# MCU.net
KiCad netlist of a schematic drawn in Altium Designer
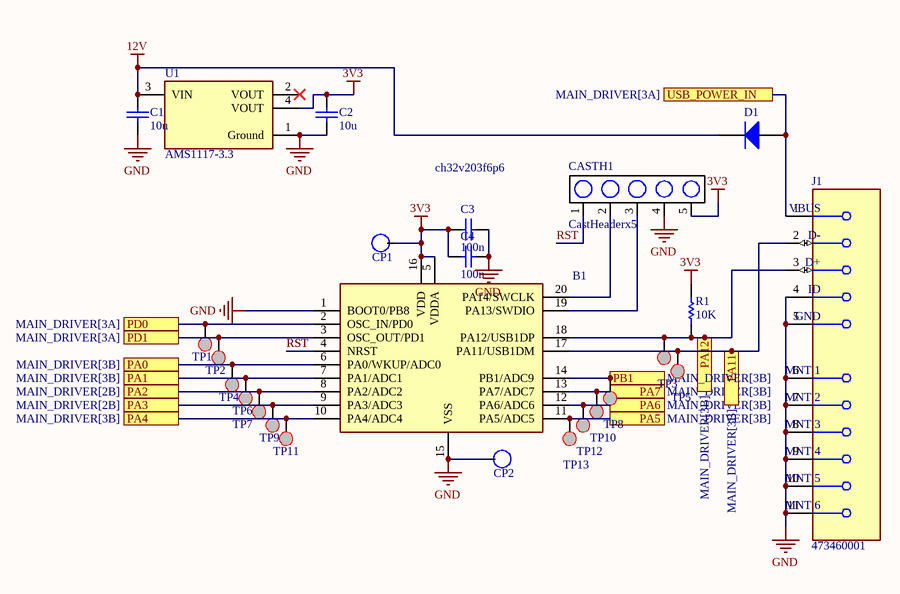
[diagram p0: MCU.SchDoc]

(export (version "E")
  (design (tool "Eeschema 10.0.6"))
  (components
    (comp (ref "B1")
      (value "ch32v203f6p6")
      (footprint "SOP65P640X110-20N")
      (description "144MHz, Industrial-grade general-purpose microcontrollers TSSOP20 Package")
      (libsource (lib "ch32v203f6p6") (part "ch32v203f6p6"))
    )
    (comp (ref "C1")
      (value "10u")
      (footprint "CAP FILM 0603_1608")
      (description "Capacitor")
      (libsource (lib "Simulation Generic Components") (part "Capacitor"))
    )
    (comp (ref "C2")
      (value "10u")
      (footprint "CAP FILM 0603_1608")
      (description "Capacitor")
      (libsource (lib "Simulation Generic Components") (part "Capacitor"))
    )
    (comp (ref "C3")
      (value "100n")
      (footprint "SMD-0603-RES")
      (description "Capacitor")
      (libsource (lib "Simulation Generic Components") (part "Capacitor"))
    )
    (comp (ref "C4")
      (value "100n")
      (footprint "SMD-0603-RES")
      (description "Capacitor")
      (libsource (lib "Simulation Generic Components") (part "Capacitor"))
    )
    (comp (ref "CASTH1")
      (value "CastHeaderx5")
      (footprint "CASTHEADERX5")
      (libsource (lib "castellated_headers") (part "CastHeaderx5"))
    )
    (comp (ref "CP1")
      (value "CONNECT_PAD")
      (footprint "PAD_SQUARE")
      (libsource (lib "solderpad") (part "CONNECT_PAD"))
    )
    (comp (ref "CP2")
      (value "CONNECT_PAD")
      (footprint "PAD_SQUARE")
      (libsource (lib "solderpad") (part "CONNECT_PAD"))
    )
    (comp (ref "D1")
      (value "FR107")
      (footprint "SODFL365X110-2N")
      (description "Diode")
      (libsource (lib "Simulation Generic Components") (part "Diode"))
    )
    (comp (ref "J1")
      (value "473460001")
      (footprint "FP-473460001-MFG")
      (description "CONN RCPT USB2.0 MICRO B SMD R/A")
      (fields
        (field (name "OCTOPART") "https://octopart.com/47346-0001-molex-7164928")
        (field (name "MANUFACTURER") "Molex")
      )
      (libsource (lib "Altium Content Vault") (part "53ae1f1d9b557310b43ca686e5bb76a"))
    )
    (comp (ref "R1")
      (value "10K")
      (footprint "SMD-0603-RES")
      (description "Resistor")
      (libsource (lib "Simulation Generic Components") (part "Resistor"))
    )
    (comp (ref "TP1") (value "~") (footprint "ROUND_SMALL") (libsource (lib "solderpad") (part "TEST_PAD")))
    (comp (ref "TP2") (value "~") (footprint "ROUND_SMALL") (libsource (lib "solderpad") (part "TEST_PAD")))
    (comp (ref "TP3") (value "~") (footprint "ROUND_SMALL") (libsource (lib "solderpad") (part "TEST_PAD")))
    (comp (ref "TP4") (value "~") (footprint "ROUND_SMALL") (libsource (lib "solderpad") (part "TEST_PAD")))
    (comp (ref "TP5") (value "~") (footprint "ROUND_SMALL") (libsource (lib "solderpad") (part "TEST_PAD")))
    (comp (ref "TP6") (value "~") (footprint "ROUND_SMALL") (libsource (lib "solderpad") (part "TEST_PAD")))
    (comp (ref "TP7") (value "~") (footprint "ROUND_SMALL") (libsource (lib "solderpad") (part "TEST_PAD")))
    (comp (ref "TP8") (value "~") (footprint "ROUND_SMALL") (libsource (lib "solderpad") (part "TEST_PAD")))
    (comp (ref "TP9") (value "~") (footprint "ROUND_SMALL") (libsource (lib "solderpad") (part "TEST_PAD")))
    (comp (ref "TP10") (value "~") (footprint "ROUND_SMALL") (libsource (lib "solderpad") (part "TEST_PAD")))
    (comp (ref "TP11") (value "~") (footprint "ROUND_SMALL") (libsource (lib "solderpad") (part "TEST_PAD")))
    (comp (ref "TP12") (value "~") (footprint "ROUND_SMALL") (libsource (lib "solderpad") (part "TEST_PAD")))
    (comp (ref "TP13") (value "~") (footprint "ROUND_SMALL") (libsource (lib "solderpad") (part "TEST_PAD")))
    (comp (ref "U1")
      (value "AMS1117-3.3")
      (footprint "FP-AMS1117-IPC_C")
      (description "LDO Voltage Regulators 1A, 3.3V")
      (fields
        (field (name "OCTOPART") "https://octopart.com/ams1117-3.3-advanced+monolithic+systems-25899300")
        (field (name "MANUFACTURER") "Advanced Monolithic Systems")
      )
      (libsource (lib "Altium Content Vault") (part "8bdbb5f8e77002000e30dd2845d0354"))
    )
  )
  (nets
    (net (code "1") (name "/PA0") (class "Default")
      (node (ref "B1") (pin "6") (pinfunction "PA0/WKUP/ADC0_6") (pintype "passive"))
      (node (ref "TP4") (pin "1") (pinfunction "Test_Point_1") (pintype "passive"))
    )
    (net (code "2") (name "/PA1") (class "Default")
      (node (ref "B1") (pin "7") (pinfunction "PA1/ADC1_7") (pintype "passive"))
      (node (ref "TP6") (pin "1") (pinfunction "Test_Point_1") (pintype "passive"))
    )
    (net (code "3") (name "/PA2") (class "Default")
      (node (ref "B1") (pin "8") (pinfunction "PA2/ADC2_8") (pintype "passive"))
      (node (ref "TP7") (pin "1") (pinfunction "Test_Point_1") (pintype "passive"))
    )
    (net (code "4") (name "/PA3") (class "Default")
      (node (ref "B1") (pin "9") (pinfunction "PA3/ADC3_9") (pintype "passive"))
      (node (ref "TP9") (pin "1") (pinfunction "Test_Point_1") (pintype "passive"))
    )
    (net (code "5") (name "/PA4") (class "Default")
      (node (ref "B1") (pin "10") (pinfunction "PA4/ADC4_10") (pintype "passive"))
      (node (ref "TP11") (pin "1") (pinfunction "Test_Point_1") (pintype "passive"))
    )
    (net (code "6") (name "/PA5") (class "Default")
      (node (ref "B1") (pin "11") (pinfunction "PA5/ADC5_11") (pintype "passive"))
      (node (ref "TP13") (pin "1") (pinfunction "Test_Point_1") (pintype "passive"))
    )
    (net (code "7") (name "/PA6") (class "Default")
      (node (ref "B1") (pin "12") (pinfunction "PA6/ADC6_12") (pintype "passive"))
      (node (ref "TP12") (pin "1") (pinfunction "Test_Point_1") (pintype "passive"))
    )
    (net (code "8") (name "/PA7") (class "Default")
      (node (ref "B1") (pin "13") (pinfunction "PA7/ADC7_13") (pintype "passive"))
      (node (ref "TP10") (pin "1") (pinfunction "Test_Point_1") (pintype "passive"))
    )
    (net (code "9") (name "/PA11") (class "Default")
      (node (ref "B1") (pin "17") (pinfunction "PA11/USB1DM_17") (pintype "passive"))
      (node (ref "J1") (pin "2") (pinfunction "D+_2") (pintype "bidirectional"))
      (node (ref "TP5") (pin "1") (pinfunction "Test_Point_1") (pintype "passive"))
    )
    (net (code "10") (name "/PA12") (class "Default")
      (node (ref "B1") (pin "18") (pinfunction "PA12/USB1DP_18") (pintype "passive"))
      (node (ref "J1") (pin "3") (pinfunction "D-_3") (pintype "bidirectional"))
      (node (ref "R1") (pin "1") (pinfunction "1_1") (pintype "passive"))
      (node (ref "TP3") (pin "1") (pinfunction "Test_Point_1") (pintype "passive"))
    )
    (net (code "11") (name "/PB1") (class "Default")
      (node (ref "B1") (pin "14") (pinfunction "PB1/ADC9_14") (pintype "passive"))
      (node (ref "TP8") (pin "1") (pinfunction "Test_Point_1") (pintype "passive"))
    )
    (net (code "12") (name "/PD0") (class "Default")
      (node (ref "B1") (pin "2") (pinfunction "OSC_IN/PD0_2") (pintype "passive"))
      (node (ref "TP1") (pin "1") (pinfunction "Test_Point_1") (pintype "passive"))
    )
    (net (code "13") (name "/PD1") (class "Default")
      (node (ref "B1") (pin "3") (pinfunction "OSC_OUT/PD1_3") (pintype "passive"))
      (node (ref "TP2") (pin "1") (pinfunction "Test_Point_1") (pintype "passive"))
    )
    (net (code "14") (name "/RST") (class "Default")
      (node (ref "B1") (pin "4") (pinfunction "NRST_4") (pintype "passive"))
      (node (ref "CASTH1") (pin "1") (pinfunction "1_1") (pintype "passive"))
    )
    (net (code "15") (name "/USB_POWER_IN") (class "Default")
      (node (ref "D1") (pin "1") (pinfunction "A_1") (pintype "passive"))
      (node (ref "J1") (pin "1") (pinfunction "VBUS_1") (pintype "power_in"))
    )
    (net (code "16") (name "3V3") (class "Default")
      (node (ref "B1") (pin "16") (pinfunction "VDD_16") (pintype "passive"))
      (node (ref "B1") (pin "5") (pinfunction "VDDA_5") (pintype "passive"))
      (node (ref "C2") (pin "2") (pinfunction "2_2") (pintype "passive"))
      (node (ref "C3") (pin "1") (pinfunction "1_1") (pintype "passive"))
      (node (ref "C4") (pin "1") (pinfunction "1_1") (pintype "passive"))
      (node (ref "CASTH1") (pin "5") (pinfunction "5_5") (pintype "passive"))
      (node (ref "CP1") (pin "1") (pinfunction "1_1") (pintype "passive"))
      (node (ref "R1") (pin "2") (pinfunction "2_2") (pintype "passive"))
      (node (ref "U1") (pin "4") (pinfunction "VOUT_4") (pintype "passive"))
    )
    (net (code "17") (name "12V") (class "Default")
      (node (ref "C1") (pin "2") (pinfunction "2_2") (pintype "passive"))
      (node (ref "D1") (pin "2") (pinfunction "K_2") (pintype "passive"))
      (node (ref "U1") (pin "3") (pinfunction "VIN_3") (pintype "power_in"))
    )
    (net (code "18") (name "GND") (class "Default")
      (node (ref "B1") (pin "1") (pinfunction "BOOT0/PB8_1") (pintype "passive"))
      (node (ref "B1") (pin "15") (pinfunction "VSS_15") (pintype "passive"))
      (node (ref "C1") (pin "1") (pinfunction "1_1") (pintype "passive"))
      (node (ref "C2") (pin "1") (pinfunction "1_1") (pintype "passive"))
      (node (ref "C3") (pin "2") (pinfunction "2_2") (pintype "passive"))
      (node (ref "C4") (pin "2") (pinfunction "2_2") (pintype "passive"))
      (node (ref "CASTH1") (pin "4") (pinfunction "4_4") (pintype "passive"))
      (node (ref "CP2") (pin "1") (pinfunction "1_1") (pintype "passive"))
      (node (ref "J1") (pin "10") (pinfunction "MNT_5_10") (pintype "passive"))
      (node (ref "J1") (pin "11") (pinfunction "MNT_6_11") (pintype "passive"))
      (node (ref "J1") (pin "4") (pinfunction "ID_4") (pintype "passive"))
      (node (ref "J1") (pin "5") (pinfunction "GND_5") (pintype "power_in"))
      (node (ref "J1") (pin "6") (pinfunction "MNT_1_6") (pintype "passive"))
      (node (ref "J1") (pin "7") (pinfunction "MNT_2_7") (pintype "passive"))
      (node (ref "J1") (pin "8") (pinfunction "MNT_3_8") (pintype "passive"))
      (node (ref "J1") (pin "9") (pinfunction "MNT_4_9") (pintype "passive"))
      (node (ref "U1") (pin "1") (pinfunction "Ground_1") (pintype "power_in"))
    )
    (net (code "19") (name "Net-(B1-PA13{slash}SWDIO)") (class "Default")
      (node (ref "B1") (pin "19") (pinfunction "PA13/SWDIO_19") (pintype "passive"))
      (node (ref "CASTH1") (pin "3") (pinfunction "3_3") (pintype "passive"))
    )
    (net (code "20") (name "Net-(B1-PA14{slash}SWCLK)") (class "Default")
      (node (ref "B1") (pin "20") (pinfunction "PA14/SWCLK_20") (pintype "passive"))
      (node (ref "CASTH1") (pin "2") (pinfunction "2_2") (pintype "passive"))
    )
    (net (code "21") (name "unconnected-(U1-VOUT-Pad2)") (class "Default")
      (node (ref "U1") (pin "2") (pinfunction "VOUT_2") (pintype "passive+no_connect"))
    )
  )
)
